# design.net
KiCad netlist of a schematic drawn in Altium Designer
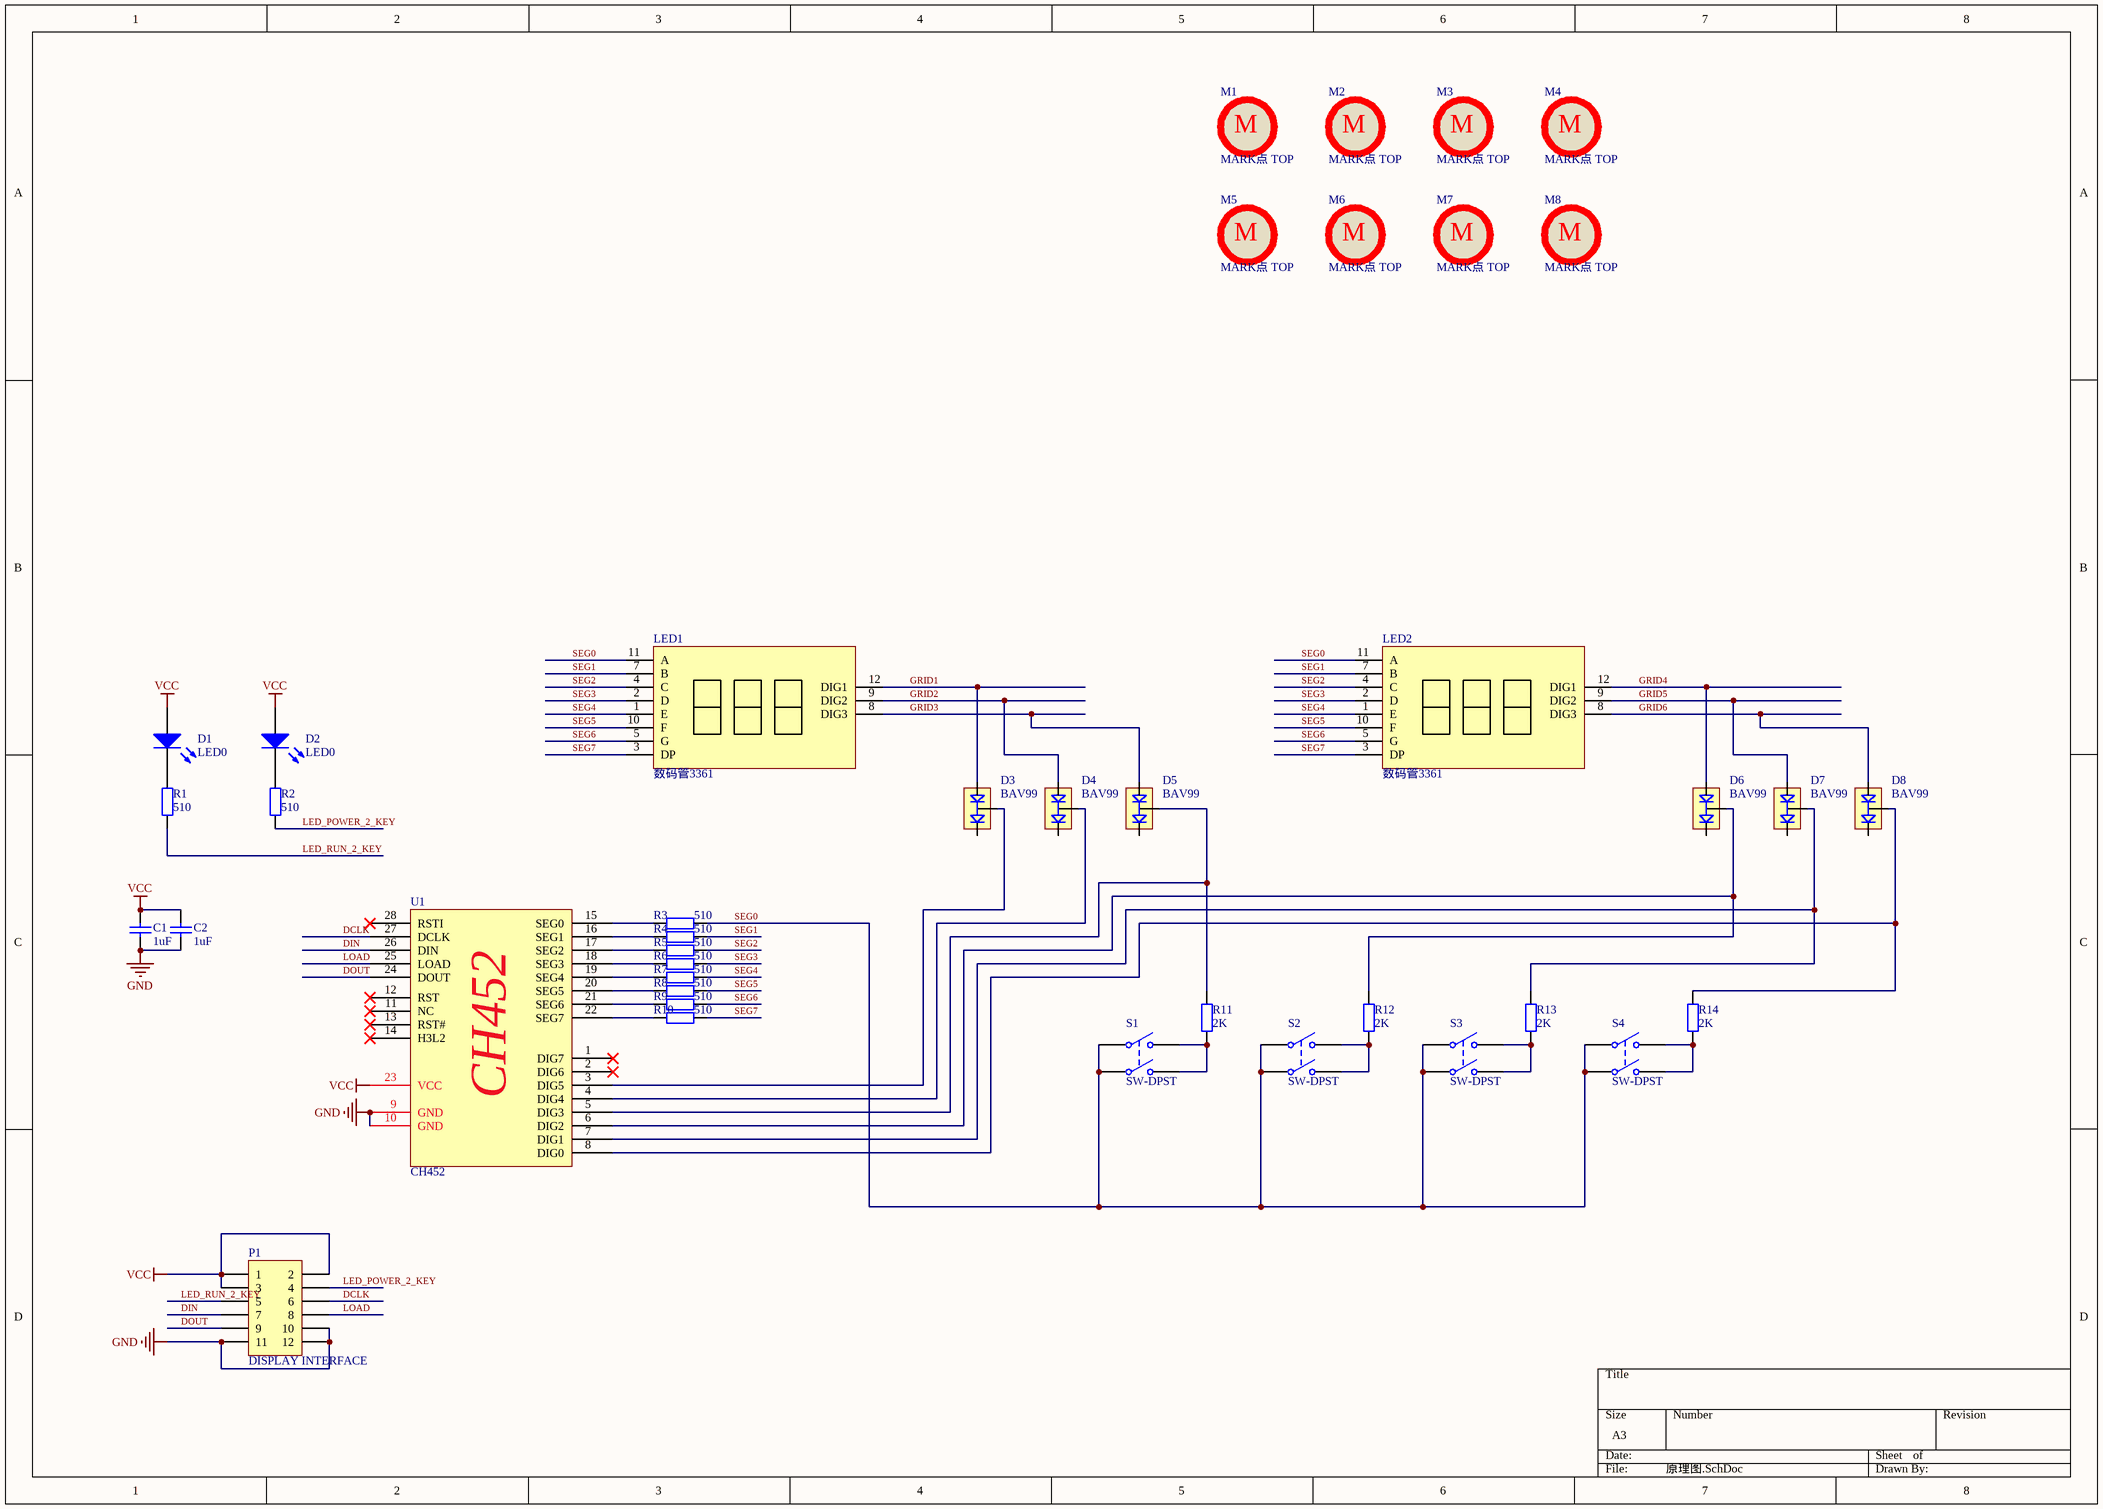
[diagram p0: 原理图.SchDoc]

(export (version "E")
  (design (tool "Eeschema 10.0.6"))
  (components
    (comp (ref "C1")
      (value "1uF")
      (footprint "C SMD 0603")
      (description "Capacitor")
      (fields (field (name "PUBLISHER") "Altium Limited"))
      (libsource (lib "Miscellaneous Devices") (part "Cap"))
    )
    (comp (ref "C2")
      (value "1uF")
      (footprint "C SMD 0603")
      (description "Capacitor")
      (fields (field (name "PUBLISHER") "Altium Limited"))
      (libsource (lib "Miscellaneous Devices") (part "Cap"))
    )
    (comp (ref "D1")
      (value "LED0")
      (footprint "LED DIP 3mm")
      (description "Typical INFRARED GaAs LED")
      (fields (field (name "PUBLISHER") "Altium Limited"))
      (libsource (lib "Miscellaneous Devices") (part "LED0"))
    )
    (comp (ref "D2")
      (value "LED0")
      (footprint "LED DIP 3mm")
      (description "Typical INFRARED GaAs LED")
      (fields (field (name "PUBLISHER") "Altium Limited"))
      (libsource (lib "Miscellaneous Devices") (part "LED0"))
    )
    (comp (ref "D3") (value "BAV99") (footprint "SOT23") (libsource (lib "mysch") (part "BAV99")))
    (comp (ref "D4") (value "BAV99") (footprint "SOT23") (libsource (lib "mysch") (part "BAV99")))
    (comp (ref "D5") (value "BAV99") (footprint "SOT23") (libsource (lib "mysch") (part "BAV99")))
    (comp (ref "D6") (value "BAV99") (footprint "SOT23") (libsource (lib "mysch") (part "BAV99")))
    (comp (ref "D7") (value "BAV99") (footprint "SOT23") (libsource (lib "mysch") (part "BAV99")))
    (comp (ref "D8") (value "BAV99") (footprint "SOT23") (libsource (lib "mysch") (part "BAV99")))
    (comp (ref "LED1") (value "数码管3361") (footprint "数码管3361") (libsource (lib "mysch") (part "数码管3361")))
    (comp (ref "LED2") (value "数码管3361") (footprint "数码管3361") (libsource (lib "mysch") (part "数码管3361")))
    (comp (ref "M1") (value "MARK点 TOP") (footprint "MARK点 TOP") (libsource (lib "mysch") (part "MARK点 TOP")))
    (comp (ref "M2") (value "MARK点 TOP") (footprint "MARK点 TOP") (libsource (lib "mysch") (part "MARK点 TOP")))
    (comp (ref "M3") (value "MARK点 TOP") (footprint "MARK点 TOP") (libsource (lib "mysch") (part "MARK点 TOP")))
    (comp (ref "M4") (value "MARK点 TOP") (footprint "MARK点 TOP") (libsource (lib "mysch") (part "MARK点 TOP")))
    (comp (ref "M5") (value "MARK点 TOP") (footprint "MARK点 TOP") (libsource (lib "mysch") (part "MARK点 TOP")))
    (comp (ref "M6") (value "MARK点 TOP") (footprint "MARK点 TOP") (libsource (lib "mysch") (part "MARK点 TOP")))
    (comp (ref "M7") (value "MARK点 TOP") (footprint "MARK点 TOP") (libsource (lib "mysch") (part "MARK点 TOP")))
    (comp (ref "M8") (value "MARK点 TOP") (footprint "MARK点 TOP") (libsource (lib "mysch") (part "MARK点 TOP")))
    (comp (ref "P1")
      (value "DISPLAY INTERFACE")
      (footprint "FFC_1.0mm_12pin_弯")
      (description "Header, 6-Pin, Dual row")
      (fields (field (name "PUBLISHER") "Altium Limited"))
      (libsource (lib "Miscellaneous Connectors") (part "Header 6X2"))
    )
    (comp (ref "R1")
      (value "510")
      (footprint "R SMD 0603")
      (description "Resistor")
      (fields (field (name "PUBLISHER") "Altium Limited"))
      (libsource (lib "") (part "Res2_1"))
    )
    (comp (ref "R2")
      (value "510")
      (footprint "R SMD 0603")
      (description "Resistor")
      (fields (field (name "PUBLISHER") "Altium Limited"))
      (libsource (lib "") (part "Res2_1"))
    )
    (comp (ref "R3")
      (value "510")
      (footprint "R SMD 0603")
      (description "Resistor")
      (fields (field (name "PUBLISHER") "Altium Limited"))
      (libsource (lib "Miscellaneous Devices") (part "Res2"))
    )
    (comp (ref "R4")
      (value "510")
      (footprint "R SMD 0603")
      (description "Resistor")
      (fields (field (name "PUBLISHER") "Altium Limited"))
      (libsource (lib "Miscellaneous Devices") (part "Res2"))
    )
    (comp (ref "R5")
      (value "510")
      (footprint "R SMD 0603")
      (description "Resistor")
      (fields (field (name "PUBLISHER") "Altium Limited"))
      (libsource (lib "Miscellaneous Devices") (part "Res2"))
    )
    (comp (ref "R6")
      (value "510")
      (footprint "R SMD 0603")
      (description "Resistor")
      (fields (field (name "PUBLISHER") "Altium Limited"))
      (libsource (lib "Miscellaneous Devices") (part "Res2"))
    )
    (comp (ref "R7")
      (value "510")
      (footprint "R SMD 0603")
      (description "Resistor")
      (fields (field (name "PUBLISHER") "Altium Limited"))
      (libsource (lib "Miscellaneous Devices") (part "Res2"))
    )
    (comp (ref "R8")
      (value "510")
      (footprint "R SMD 0603")
      (description "Resistor")
      (fields (field (name "PUBLISHER") "Altium Limited"))
      (libsource (lib "Miscellaneous Devices") (part "Res2"))
    )
    (comp (ref "R9")
      (value "510")
      (footprint "R SMD 0603")
      (description "Resistor")
      (fields (field (name "PUBLISHER") "Altium Limited"))
      (libsource (lib "Miscellaneous Devices") (part "Res2"))
    )
    (comp (ref "R10")
      (value "510")
      (footprint "R SMD 0603")
      (description "Resistor")
      (fields (field (name "PUBLISHER") "Altium Limited"))
      (libsource (lib "Miscellaneous Devices") (part "Res2"))
    )
    (comp (ref "R11")
      (value "2K")
      (footprint "R SMD 0603")
      (description "Resistor")
      (fields (field (name "PUBLISHER") "Altium Limited"))
      (libsource (lib "") (part "Res2_1"))
    )
    (comp (ref "R12")
      (value "2K")
      (footprint "R SMD 0603")
      (description "Resistor")
      (fields (field (name "PUBLISHER") "Altium Limited"))
      (libsource (lib "") (part "Res2_1"))
    )
    (comp (ref "R13")
      (value "2K")
      (footprint "R SMD 0603")
      (description "Resistor")
      (fields (field (name "PUBLISHER") "Altium Limited"))
      (libsource (lib "") (part "Res2_1"))
    )
    (comp (ref "R14")
      (value "2K")
      (footprint "R SMD 0603")
      (description "Resistor")
      (fields (field (name "PUBLISHER") "Altium Limited"))
      (libsource (lib "") (part "Res2_1"))
    )
    (comp (ref "S1")
      (value "SW-DPST")
      (footprint "按键 标准型 6*6mm")
      (description "Double-Pole, Single-Throw Switch")
      (fields (field (name "PUBLISHER") "Altium Limited"))
      (libsource (lib "Miscellaneous Devices") (part "SW-DPST"))
    )
    (comp (ref "S2")
      (value "SW-DPST")
      (footprint "按键 标准型 6*6mm")
      (description "Double-Pole, Single-Throw Switch")
      (fields (field (name "PUBLISHER") "Altium Limited"))
      (libsource (lib "Miscellaneous Devices") (part "SW-DPST"))
    )
    (comp (ref "S3")
      (value "SW-DPST")
      (footprint "按键 标准型 6*6mm")
      (description "Double-Pole, Single-Throw Switch")
      (fields (field (name "PUBLISHER") "Altium Limited"))
      (libsource (lib "Miscellaneous Devices") (part "SW-DPST"))
    )
    (comp (ref "S4")
      (value "SW-DPST")
      (footprint "按键 标准型 6*6mm")
      (description "Double-Pole, Single-Throw Switch")
      (fields (field (name "PUBLISHER") "Altium Limited"))
      (libsource (lib "Miscellaneous Devices") (part "SW-DPST"))
    )
    (comp (ref "U1") (value "CH452") (footprint "SO28_N") (libsource (lib "display_board") (part "CH452")))
  )
  (nets
    (net (code "1") (name "/DCLK") (class "Default")
      (node (ref "P1") (pin "6") (pinfunction "6_6") (pintype "passive"))
      (node (ref "U1") (pin "27") (pinfunction "DCLK_27") (pintype "passive"))
    )
    (net (code "2") (name "/DIN") (class "Default")
      (node (ref "P1") (pin "7") (pinfunction "7_7") (pintype "passive"))
      (node (ref "U1") (pin "26") (pinfunction "DIN_26") (pintype "passive"))
    )
    (net (code "3") (name "/DOUT") (class "Default")
      (node (ref "P1") (pin "9") (pinfunction "9_9") (pintype "passive"))
      (node (ref "U1") (pin "24") (pinfunction "DOUT_24") (pintype "passive"))
    )
    (net (code "4") (name "/GRID1") (class "Default")
      (node (ref "D3") (pin "1") (pinfunction "1_1") (pintype "passive"))
      (node (ref "LED1") (pin "12") (pinfunction "DIG1_12") (pintype "passive"))
    )
    (net (code "5") (name "/GRID2") (class "Default")
      (node (ref "D4") (pin "1") (pinfunction "1_1") (pintype "passive"))
      (node (ref "LED1") (pin "9") (pinfunction "DIG2_9") (pintype "passive"))
    )
    (net (code "6") (name "/GRID3") (class "Default")
      (node (ref "D5") (pin "1") (pinfunction "1_1") (pintype "passive"))
      (node (ref "LED1") (pin "8") (pinfunction "DIG3_8") (pintype "passive"))
    )
    (net (code "7") (name "/GRID4") (class "Default")
      (node (ref "D6") (pin "1") (pinfunction "1_1") (pintype "passive"))
      (node (ref "LED2") (pin "12") (pinfunction "DIG1_12") (pintype "passive"))
    )
    (net (code "8") (name "/GRID5") (class "Default")
      (node (ref "D7") (pin "1") (pinfunction "1_1") (pintype "passive"))
      (node (ref "LED2") (pin "9") (pinfunction "DIG2_9") (pintype "passive"))
    )
    (net (code "9") (name "/GRID6") (class "Default")
      (node (ref "D8") (pin "1") (pinfunction "1_1") (pintype "passive"))
      (node (ref "LED2") (pin "8") (pinfunction "DIG3_8") (pintype "passive"))
    )
    (net (code "10") (name "/LED_POWER_2_KEY") (class "Default")
      (node (ref "P1") (pin "4") (pinfunction "4_4") (pintype "passive"))
      (node (ref "R2") (pin "2") (pinfunction "2_2") (pintype "passive"))
    )
    (net (code "11") (name "/LED_RUN_2_KEY") (class "Default")
      (node (ref "P1") (pin "5") (pinfunction "5_5") (pintype "passive"))
      (node (ref "R1") (pin "2") (pinfunction "2_2") (pintype "passive"))
    )
    (net (code "12") (name "/LOAD") (class "Default")
      (node (ref "P1") (pin "8") (pinfunction "8_8") (pintype "passive"))
      (node (ref "U1") (pin "25") (pinfunction "LOAD_25") (pintype "passive"))
    )
    (net (code "13") (name "/SEG0") (class "Default")
      (node (ref "LED1") (pin "11") (pinfunction "A_11") (pintype "passive"))
      (node (ref "LED2") (pin "11") (pinfunction "A_11") (pintype "passive"))
      (node (ref "R3") (pin "1") (pinfunction "1_1") (pintype "passive"))
      (node (ref "S1") (pin "1") (pinfunction "COMMON1_1") (pintype "passive"))
      (node (ref "S1") (pin "3") (pinfunction "COMMON2_3") (pintype "passive"))
      (node (ref "S2") (pin "1") (pinfunction "COMMON1_1") (pintype "passive"))
      (node (ref "S2") (pin "3") (pinfunction "COMMON2_3") (pintype "passive"))
      (node (ref "S3") (pin "1") (pinfunction "COMMON1_1") (pintype "passive"))
      (node (ref "S3") (pin "3") (pinfunction "COMMON2_3") (pintype "passive"))
      (node (ref "S4") (pin "1") (pinfunction "COMMON1_1") (pintype "passive"))
      (node (ref "S4") (pin "3") (pinfunction "COMMON2_3") (pintype "passive"))
    )
    (net (code "14") (name "/SEG1") (class "Default")
      (node (ref "LED1") (pin "7") (pinfunction "B_7") (pintype "passive"))
      (node (ref "LED2") (pin "7") (pinfunction "B_7") (pintype "passive"))
      (node (ref "R4") (pin "1") (pinfunction "1_1") (pintype "passive"))
    )
    (net (code "15") (name "/SEG2") (class "Default")
      (node (ref "LED1") (pin "4") (pinfunction "C_4") (pintype "passive"))
      (node (ref "LED2") (pin "4") (pinfunction "C_4") (pintype "passive"))
      (node (ref "R5") (pin "1") (pinfunction "1_1") (pintype "passive"))
    )
    (net (code "16") (name "/SEG3") (class "Default")
      (node (ref "LED1") (pin "2") (pinfunction "D_2") (pintype "passive"))
      (node (ref "LED2") (pin "2") (pinfunction "D_2") (pintype "passive"))
      (node (ref "R6") (pin "1") (pinfunction "1_1") (pintype "passive"))
    )
    (net (code "17") (name "/SEG4") (class "Default")
      (node (ref "LED1") (pin "1") (pinfunction "E_1") (pintype "passive"))
      (node (ref "LED2") (pin "1") (pinfunction "E_1") (pintype "passive"))
      (node (ref "R7") (pin "1") (pinfunction "1_1") (pintype "passive"))
    )
    (net (code "18") (name "/SEG5") (class "Default")
      (node (ref "LED1") (pin "10") (pinfunction "F_10") (pintype "passive"))
      (node (ref "LED2") (pin "10") (pinfunction "F_10") (pintype "passive"))
      (node (ref "R8") (pin "1") (pinfunction "1_1") (pintype "passive"))
    )
    (net (code "19") (name "/SEG6") (class "Default")
      (node (ref "LED1") (pin "5") (pinfunction "G_5") (pintype "passive"))
      (node (ref "LED2") (pin "5") (pinfunction "G_5") (pintype "passive"))
      (node (ref "R9") (pin "1") (pinfunction "1_1") (pintype "passive"))
    )
    (net (code "20") (name "/SEG7") (class "Default")
      (node (ref "LED1") (pin "3") (pinfunction "DP_3") (pintype "passive"))
      (node (ref "LED2") (pin "3") (pinfunction "DP_3") (pintype "passive"))
      (node (ref "R10") (pin "1") (pinfunction "1_1") (pintype "passive"))
    )
    (net (code "21") (name "GND") (class "Default")
      (node (ref "C1") (pin "2") (pinfunction "2_2") (pintype "passive"))
      (node (ref "C2") (pin "2") (pinfunction "2_2") (pintype "passive"))
      (node (ref "P1") (pin "10") (pinfunction "10_10") (pintype "passive"))
      (node (ref "P1") (pin "11") (pinfunction "11_11") (pintype "passive"))
      (node (ref "P1") (pin "12") (pinfunction "12_12") (pintype "passive"))
      (node (ref "U1") (pin "10") (pinfunction "GND_10") (pintype "power_in"))
      (node (ref "U1") (pin "9") (pinfunction "GND_9") (pintype "power_in"))
    )
    (net (code "22") (name "Net-(D1-K)") (class "Default")
      (node (ref "D1") (pin "2") (pinfunction "K_2") (pintype "passive"))
      (node (ref "R1") (pin "1") (pinfunction "1_1") (pintype "passive"))
    )
    (net (code "23") (name "Net-(D2-K)") (class "Default")
      (node (ref "D2") (pin "2") (pinfunction "K_2") (pintype "passive"))
      (node (ref "R2") (pin "1") (pinfunction "1_1") (pintype "passive"))
    )
    (net (code "24") (name "Net-(S1-NO1)") (class "Default")
      (node (ref "R11") (pin "2") (pinfunction "2_2") (pintype "passive"))
      (node (ref "S1") (pin "2") (pinfunction "NO1_2") (pintype "passive"))
      (node (ref "S1") (pin "4") (pinfunction "NO2_4") (pintype "passive"))
    )
    (net (code "25") (name "Net-(S2-NO1)") (class "Default")
      (node (ref "R12") (pin "2") (pinfunction "2_2") (pintype "passive"))
      (node (ref "S2") (pin "2") (pinfunction "NO1_2") (pintype "passive"))
      (node (ref "S2") (pin "4") (pinfunction "NO2_4") (pintype "passive"))
    )
    (net (code "26") (name "Net-(S3-NO1)") (class "Default")
      (node (ref "R13") (pin "2") (pinfunction "2_2") (pintype "passive"))
      (node (ref "S3") (pin "2") (pinfunction "NO1_2") (pintype "passive"))
      (node (ref "S3") (pin "4") (pinfunction "NO2_4") (pintype "passive"))
    )
    (net (code "27") (name "Net-(S4-NO1)") (class "Default")
      (node (ref "R14") (pin "2") (pinfunction "2_2") (pintype "passive"))
      (node (ref "S4") (pin "2") (pinfunction "NO1_2") (pintype "passive"))
      (node (ref "S4") (pin "4") (pinfunction "NO2_4") (pintype "passive"))
    )
    (net (code "28") (name "Net-(U1-DIG0)") (class "Default")
      (node (ref "D8") (pin "3") (pinfunction "3_3") (pintype "passive"))
      (node (ref "R14") (pin "1") (pinfunction "1_1") (pintype "passive"))
      (node (ref "U1") (pin "8") (pinfunction "DIG0_8") (pintype "passive"))
    )
    (net (code "29") (name "Net-(U1-DIG1)") (class "Default")
      (node (ref "D7") (pin "3") (pinfunction "3_3") (pintype "passive"))
      (node (ref "R13") (pin "1") (pinfunction "1_1") (pintype "passive"))
      (node (ref "U1") (pin "7") (pinfunction "DIG1_7") (pintype "passive"))
    )
    (net (code "30") (name "Net-(U1-DIG2)") (class "Default")
      (node (ref "D6") (pin "3") (pinfunction "3_3") (pintype "passive"))
      (node (ref "R12") (pin "1") (pinfunction "1_1") (pintype "passive"))
      (node (ref "U1") (pin "6") (pinfunction "DIG2_6") (pintype "passive"))
    )
    (net (code "31") (name "Net-(U1-DIG3)") (class "Default")
      (node (ref "D5") (pin "3") (pinfunction "3_3") (pintype "passive"))
      (node (ref "R11") (pin "1") (pinfunction "1_1") (pintype "passive"))
      (node (ref "U1") (pin "5") (pinfunction "DIG3_5") (pintype "passive"))
    )
    (net (code "32") (name "Net-(U1-DIG4)") (class "Default")
      (node (ref "D4") (pin "3") (pinfunction "3_3") (pintype "passive"))
      (node (ref "U1") (pin "4") (pinfunction "DIG4_4") (pintype "passive"))
    )
    (net (code "33") (name "Net-(U1-DIG5)") (class "Default")
      (node (ref "D3") (pin "3") (pinfunction "3_3") (pintype "passive"))
      (node (ref "U1") (pin "3") (pinfunction "DIG5_3") (pintype "passive"))
    )
    (net (code "34") (name "Net-(U1-SEG0)") (class "Default")
      (node (ref "R3") (pin "2") (pinfunction "2_2") (pintype "passive"))
      (node (ref "U1") (pin "15") (pinfunction "SEG0_15") (pintype "passive"))
    )
    (net (code "35") (name "Net-(U1-SEG1)") (class "Default")
      (node (ref "R4") (pin "2") (pinfunction "2_2") (pintype "passive"))
      (node (ref "U1") (pin "16") (pinfunction "SEG1_16") (pintype "passive"))
    )
    (net (code "36") (name "Net-(U1-SEG2)") (class "Default")
      (node (ref "R5") (pin "2") (pinfunction "2_2") (pintype "passive"))
      (node (ref "U1") (pin "17") (pinfunction "SEG2_17") (pintype "passive"))
    )
    (net (code "37") (name "Net-(U1-SEG3)") (class "Default")
      (node (ref "R6") (pin "2") (pinfunction "2_2") (pintype "passive"))
      (node (ref "U1") (pin "18") (pinfunction "SEG3_18") (pintype "passive"))
    )
    (net (code "38") (name "Net-(U1-SEG4)") (class "Default")
      (node (ref "R7") (pin "2") (pinfunction "2_2") (pintype "passive"))
      (node (ref "U1") (pin "19") (pinfunction "SEG4_19") (pintype "passive"))
    )
    (net (code "39") (name "Net-(U1-SEG5)") (class "Default")
      (node (ref "R8") (pin "2") (pinfunction "2_2") (pintype "passive"))
      (node (ref "U1") (pin "20") (pinfunction "SEG5_20") (pintype "passive"))
    )
    (net (code "40") (name "Net-(U1-SEG6)") (class "Default")
      (node (ref "R9") (pin "2") (pinfunction "2_2") (pintype "passive"))
      (node (ref "U1") (pin "21") (pinfunction "SEG6_21") (pintype "passive"))
    )
    (net (code "41") (name "Net-(U1-SEG7)") (class "Default")
      (node (ref "R10") (pin "2") (pinfunction "2_2") (pintype "passive"))
      (node (ref "U1") (pin "22") (pinfunction "SEG7_22") (pintype "passive"))
    )
    (net (code "42") (name "VCC") (class "Default")
      (node (ref "C1") (pin "1") (pinfunction "1_1") (pintype "passive"))
      (node (ref "C2") (pin "1") (pinfunction "1_1") (pintype "passive"))
      (node (ref "D1") (pin "1") (pinfunction "A_1") (pintype "passive"))
      (node (ref "D2") (pin "1") (pinfunction "A_1") (pintype "passive"))
      (node (ref "P1") (pin "1") (pinfunction "1_1") (pintype "passive"))
      (node (ref "P1") (pin "2") (pinfunction "2_2") (pintype "passive"))
      (node (ref "P1") (pin "3") (pinfunction "3_3") (pintype "passive"))
      (node (ref "U1") (pin "23") (pinfunction "VCC_23") (pintype "power_in"))
    )
    (net (code "43") (name "unconnected-(D3-Pad2)") (class "Default")
      (node (ref "D3") (pin "2") (pinfunction "2_2") (pintype "passive"))
    )
    (net (code "44") (name "unconnected-(D4-Pad2)") (class "Default")
      (node (ref "D4") (pin "2") (pinfunction "2_2") (pintype "passive"))
    )
    (net (code "45") (name "unconnected-(D5-Pad2)") (class "Default")
      (node (ref "D5") (pin "2") (pinfunction "2_2") (pintype "passive"))
    )
    (net (code "46") (name "unconnected-(D6-Pad2)") (class "Default")
      (node (ref "D6") (pin "2") (pinfunction "2_2") (pintype "passive"))
    )
    (net (code "47") (name "unconnected-(D7-Pad2)") (class "Default")
      (node (ref "D7") (pin "2") (pinfunction "2_2") (pintype "passive"))
    )
    (net (code "48") (name "unconnected-(D8-Pad2)") (class "Default")
      (node (ref "D8") (pin "2") (pinfunction "2_2") (pintype "passive"))
    )
    (net (code "49") (name "unconnected-(M1-Pad1)") (class "Default")
      (node (ref "M1") (pin "1") (pinfunction "1_1") (pintype "passive"))
    )
    (net (code "50") (name "unconnected-(M2-Pad1)") (class "Default")
      (node (ref "M2") (pin "1") (pinfunction "1_1") (pintype "passive"))
    )
    (net (code "51") (name "unconnected-(M3-Pad1)") (class "Default")
      (node (ref "M3") (pin "1") (pinfunction "1_1") (pintype "passive"))
    )
    (net (code "52") (name "unconnected-(M4-Pad1)") (class "Default")
      (node (ref "M4") (pin "1") (pinfunction "1_1") (pintype "passive"))
    )
    (net (code "53") (name "unconnected-(M5-Pad1)") (class "Default")
      (node (ref "M5") (pin "1") (pinfunction "1_1") (pintype "passive"))
    )
    (net (code "54") (name "unconnected-(M6-Pad1)") (class "Default")
      (node (ref "M6") (pin "1") (pinfunction "1_1") (pintype "passive"))
    )
    (net (code "55") (name "unconnected-(M7-Pad1)") (class "Default")
      (node (ref "M7") (pin "1") (pinfunction "1_1") (pintype "passive"))
    )
    (net (code "56") (name "unconnected-(M8-Pad1)") (class "Default")
      (node (ref "M8") (pin "1") (pinfunction "1_1") (pintype "passive"))
    )
    (net (code "57") (name "unconnected-(U1-DIG6-Pad2)") (class "Default")
      (node (ref "U1") (pin "2") (pinfunction "DIG6_2") (pintype "passive+no_connect"))
    )
    (net (code "58") (name "unconnected-(U1-DIG7-Pad1)") (class "Default")
      (node (ref "U1") (pin "1") (pinfunction "DIG7_1") (pintype "passive+no_connect"))
    )
    (net (code "59") (name "unconnected-(U1-H3L2-Pad14)") (class "Default")
      (node (ref "U1") (pin "14") (pinfunction "H3L2_14") (pintype "passive+no_connect"))
    )
    (net (code "60") (name "unconnected-(U1-NC-Pad11)") (class "Default")
      (node (ref "U1") (pin "11") (pinfunction "NC_11") (pintype "passive+no_connect"))
    )
    (net (code "61") (name "unconnected-(U1-RST#-Pad13)") (class "Default")
      (node (ref "U1") (pin "13") (pinfunction "RST#_13") (pintype "passive+no_connect"))
    )
    (net (code "62") (name "unconnected-(U1-RST-Pad12)") (class "Default")
      (node (ref "U1") (pin "12") (pinfunction "RST_12") (pintype "passive+no_connect"))
    )
    (net (code "63") (name "unconnected-(U1-RSTI-Pad28)") (class "Default")
      (node (ref "U1") (pin "28") (pinfunction "RSTI_28") (pintype "passive+no_connect"))
    )
  )
)
